# w5500_spi.net
KiCad netlist of a schematic drawn in EAGLE
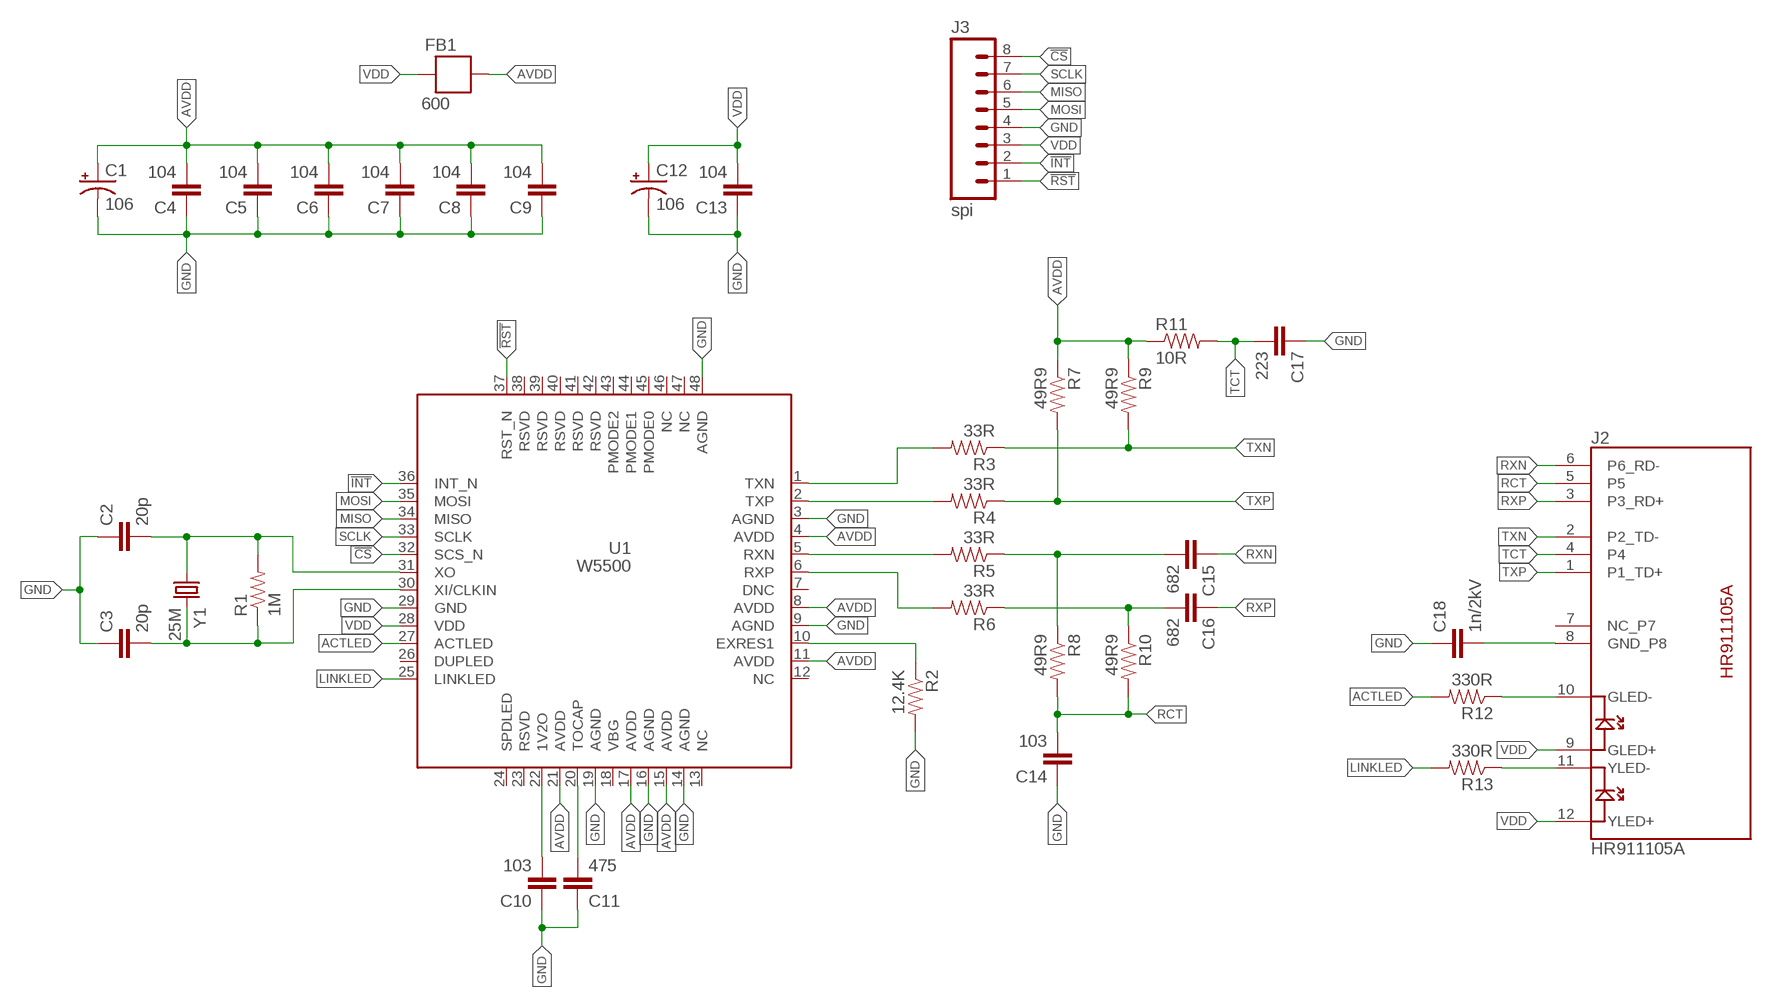
[diagram p0: schematic, sheet 1]

(export (version "E")
  (design (tool "Eeschema 10.0.6"))
  (components
    (comp (ref "C1")
      (value "106")
      (footprint "eagle-import:EIA3216")
      (libsource (lib "eagle-import") (part "CAP_POL1206"))
    )
    (comp (ref "C2")
      (value "20p")
      (footprint "eagle-import:0603-CAP")
      (libsource (lib "eagle-import") (part "z_jlc_smt_CAP0603-CAP"))
    )
    (comp (ref "C3")
      (value "20p")
      (footprint "eagle-import:0603-CAP")
      (libsource (lib "eagle-import") (part "z_jlc_smt_CAP0603-CAP"))
    )
    (comp (ref "C4")
      (value "104")
      (footprint "eagle-import:0603-CAP")
      (libsource (lib "eagle-import") (part "CAP0603-CAP"))
    )
    (comp (ref "C5")
      (value "104")
      (footprint "eagle-import:0603-CAP")
      (libsource (lib "eagle-import") (part "z_jlc_smt_CAP0603-CAP"))
    )
    (comp (ref "C6")
      (value "104")
      (footprint "eagle-import:0603-CAP")
      (libsource (lib "eagle-import") (part "z_jlc_smt_CAP0603-CAP"))
    )
    (comp (ref "C7")
      (value "104")
      (footprint "eagle-import:0603-CAP")
      (libsource (lib "eagle-import") (part "z_jlc_smt_CAP0603-CAP"))
    )
    (comp (ref "C8")
      (value "104")
      (footprint "eagle-import:0603-CAP")
      (libsource (lib "eagle-import") (part "z_jlc_smt_CAP0603-CAP"))
    )
    (comp (ref "C9")
      (value "104")
      (footprint "eagle-import:0603-CAP")
      (libsource (lib "eagle-import") (part "z_jlc_smt_CAP0603-CAP"))
    )
    (comp (ref "C10")
      (value "103")
      (footprint "eagle-import:0603-CAP")
      (libsource (lib "eagle-import") (part "z_jlc_smt_CAP0603-CAP"))
    )
    (comp (ref "C11")
      (value "475")
      (footprint "eagle-import:0603-CAP")
      (libsource (lib "eagle-import") (part "z_jlc_smt_CAP0603-CAP"))
    )
    (comp (ref "C12")
      (value "106")
      (footprint "eagle-import:EIA3216")
      (libsource (lib "eagle-import") (part "CAP_POL1206"))
    )
    (comp (ref "C13")
      (value "104")
      (footprint "eagle-import:0603-CAP")
      (libsource (lib "eagle-import") (part "z_jlc_smt_CAP0603-CAP"))
    )
    (comp (ref "C14")
      (value "103")
      (footprint "eagle-import:0603-CAP")
      (libsource (lib "eagle-import") (part "z_jlc_smt_CAP0603-CAP"))
    )
    (comp (ref "C15")
      (value "682")
      (footprint "eagle-import:0603-CAP")
      (libsource (lib "eagle-import") (part "z_jlc_smt_CAP0603-CAP"))
    )
    (comp (ref "C16")
      (value "682")
      (footprint "eagle-import:0603-CAP")
      (libsource (lib "eagle-import") (part "z_jlc_smt_CAP0603-CAP"))
    )
    (comp (ref "C17")
      (value "223")
      (footprint "eagle-import:0603-CAP")
      (libsource (lib "eagle-import") (part "z_jlc_smt_CAP0603-CAP"))
    )
    (comp (ref "C18")
      (value "1n/2kV")
      (footprint "eagle-import:1206")
      (libsource (lib "eagle-import") (part "z_jlc_smt_CAP1206"))
    )
    (comp (ref "FB1")
      (value "600")
      (footprint "eagle-import:0805")
      (libsource (lib "eagle-import") (part "FB0805"))
    )
    (comp (ref "J2")
      (value "HR911105A")
      (footprint "eagle-import:HR911105A")
      (libsource (lib "eagle-import") (part "HR911105A"))
    )
    (comp (ref "J3")
      (value "spi")
      (footprint "eagle-import:1X08_PIN1_NO_SILK")
      (libsource (lib "eagle-import") (part "M08NO_SILK"))
    )
    (comp (ref "R1")
      (value "1M")
      (footprint "eagle-import:0603-RES")
      (libsource (lib "eagle-import") (part "z_jlc_smt_RESISTOR0603"))
    )
    (comp (ref "R2")
      (value "12.4K")
      (footprint "eagle-import:0603-RES")
      (libsource (lib "eagle-import") (part "z_jlc_smt_RESISTOR0603"))
    )
    (comp (ref "R3")
      (value "33R")
      (footprint "eagle-import:0603-RES")
      (libsource (lib "eagle-import") (part "RESISTOR0603-RES"))
    )
    (comp (ref "R4")
      (value "33R")
      (footprint "eagle-import:0603-RES")
      (libsource (lib "eagle-import") (part "z_jlc_smt_RESISTOR0603"))
    )
    (comp (ref "R5")
      (value "33R")
      (footprint "eagle-import:0603-RES")
      (libsource (lib "eagle-import") (part "z_jlc_smt_RESISTOR0603"))
    )
    (comp (ref "R6")
      (value "33R")
      (footprint "eagle-import:0603-RES")
      (libsource (lib "eagle-import") (part "z_jlc_smt_RESISTOR0603"))
    )
    (comp (ref "R7")
      (value "49R9")
      (footprint "eagle-import:0603-RES")
      (libsource (lib "eagle-import") (part "z_jlc_smt_RESISTOR0603"))
    )
    (comp (ref "R8")
      (value "49R9")
      (footprint "eagle-import:0603-RES")
      (libsource (lib "eagle-import") (part "z_jlc_smt_RESISTOR0603"))
    )
    (comp (ref "R9")
      (value "49R9")
      (footprint "eagle-import:0603-RES")
      (libsource (lib "eagle-import") (part "z_jlc_smt_RESISTOR0603"))
    )
    (comp (ref "R10")
      (value "49R9")
      (footprint "eagle-import:0603-RES")
      (libsource (lib "eagle-import") (part "z_jlc_smt_RESISTOR0603"))
    )
    (comp (ref "R11")
      (value "10R")
      (footprint "eagle-import:0603-RES")
      (libsource (lib "eagle-import") (part "z_jlc_smt_RESISTOR0603"))
    )
    (comp (ref "R12")
      (value "330R")
      (footprint "eagle-import:0603-RES")
      (libsource (lib "eagle-import") (part "z_jlc_smt_RESISTOR0603"))
    )
    (comp (ref "R13")
      (value "330R")
      (footprint "eagle-import:0603-RES")
      (libsource (lib "eagle-import") (part "z_jlc_smt_RESISTOR0603"))
    )
    (comp (ref "U1")
      (value "W5500")
      (footprint "eagle-import:LQFP-48")
      (libsource (lib "eagle-import") (part "W5500"))
    )
    (comp (ref "Y1")
      (value "25M")
      (footprint "eagle-import:HC49US")
      (libsource (lib "eagle-import") (part "CRYSTALHC49US"))
    )
  )
  (nets
    (net (code "1") (name "/~{CS}") (class "Default")
      (node (ref "J3") (pin "8") (pinfunction "8_8") (pintype "passive"))
      (node (ref "U1") (pin "32") (pinfunction "SCS_N_32") (pintype "passive"))
    )
    (net (code "2") (name "/~{INT}") (class "Default")
      (node (ref "J3") (pin "2") (pinfunction "2_2") (pintype "passive"))
      (node (ref "U1") (pin "36") (pinfunction "INT_N_36") (pintype "passive"))
    )
    (net (code "3") (name "/~{RST}") (class "Default")
      (node (ref "J3") (pin "1") (pinfunction "1_1") (pintype "passive"))
      (node (ref "U1") (pin "37") (pinfunction "RST_N_37") (pintype "passive"))
    )
    (net (code "4") (name "ACTLED") (class "Default")
      (node (ref "R12") (pin "2") (pinfunction "2_2") (pintype "passive"))
      (node (ref "U1") (pin "27") (pinfunction "ACTLED_27") (pintype "passive"))
    )
    (net (code "5") (name "AVDD") (class "Default")
      (node (ref "C1") (pin "A") (pinfunction "+_A") (pintype "passive"))
      (node (ref "C4") (pin "2") (pinfunction "2_2") (pintype "passive"))
      (node (ref "C5") (pin "2") (pinfunction "2_2") (pintype "passive"))
      (node (ref "C6") (pin "2") (pinfunction "2_2") (pintype "passive"))
      (node (ref "C7") (pin "2") (pinfunction "2_2") (pintype "passive"))
      (node (ref "C8") (pin "2") (pinfunction "2_2") (pintype "passive"))
      (node (ref "C9") (pin "2") (pinfunction "2_2") (pintype "passive"))
      (node (ref "FB1") (pin "1") (pinfunction "P$1_1") (pintype "bidirectional"))
      (node (ref "R11") (pin "1") (pinfunction "1_1") (pintype "passive"))
      (node (ref "R7") (pin "1") (pinfunction "1_1") (pintype "passive"))
      (node (ref "R9") (pin "1") (pinfunction "1_1") (pintype "passive"))
      (node (ref "U1") (pin "11") (pinfunction "AVDD_11") (pintype "passive"))
      (node (ref "U1") (pin "15") (pinfunction "AVDD_15") (pintype "passive"))
      (node (ref "U1") (pin "17") (pinfunction "AVDD_17") (pintype "passive"))
      (node (ref "U1") (pin "21") (pinfunction "AVDD_21") (pintype "passive"))
      (node (ref "U1") (pin "4") (pinfunction "AVDD_4") (pintype "passive"))
      (node (ref "U1") (pin "8") (pinfunction "AVDD_8") (pintype "passive"))
    )
    (net (code "6") (name "GND") (class "Default")
      (node (ref "C1") (pin "C") (pinfunction "-_C") (pintype "passive"))
      (node (ref "C10") (pin "1") (pinfunction "1_1") (pintype "passive"))
      (node (ref "C11") (pin "1") (pinfunction "1_1") (pintype "passive"))
      (node (ref "C12") (pin "C") (pinfunction "-_C") (pintype "passive"))
      (node (ref "C13") (pin "1") (pinfunction "1_1") (pintype "passive"))
      (node (ref "C14") (pin "1") (pinfunction "1_1") (pintype "passive"))
      (node (ref "C17") (pin "1") (pinfunction "1_1") (pintype "passive"))
      (node (ref "C18") (pin "1") (pinfunction "1_1") (pintype "passive"))
      (node (ref "C2") (pin "1") (pinfunction "1_1") (pintype "passive"))
      (node (ref "C3") (pin "1") (pinfunction "1_1") (pintype "passive"))
      (node (ref "C4") (pin "1") (pinfunction "1_1") (pintype "passive"))
      (node (ref "C5") (pin "1") (pinfunction "1_1") (pintype "passive"))
      (node (ref "C6") (pin "1") (pinfunction "1_1") (pintype "passive"))
      (node (ref "C7") (pin "1") (pinfunction "1_1") (pintype "passive"))
      (node (ref "C8") (pin "1") (pinfunction "1_1") (pintype "passive"))
      (node (ref "C9") (pin "1") (pinfunction "1_1") (pintype "passive"))
      (node (ref "J3") (pin "4") (pinfunction "4_4") (pintype "passive"))
      (node (ref "R2") (pin "2") (pinfunction "2_2") (pintype "passive"))
      (node (ref "U1") (pin "14") (pinfunction "AGND_14") (pintype "passive"))
      (node (ref "U1") (pin "16") (pinfunction "AGND_16") (pintype "passive"))
      (node (ref "U1") (pin "19") (pinfunction "AGND_19") (pintype "passive"))
      (node (ref "U1") (pin "29") (pinfunction "GND_29") (pintype "passive"))
      (node (ref "U1") (pin "3") (pinfunction "AGND_3") (pintype "passive"))
      (node (ref "U1") (pin "48") (pinfunction "AGND_48") (pintype "passive"))
      (node (ref "U1") (pin "9") (pinfunction "AGND_9") (pintype "passive"))
    )
    (net (code "7") (name "LINKLED") (class "Default")
      (node (ref "R13") (pin "2") (pinfunction "2_2") (pintype "passive"))
      (node (ref "U1") (pin "25") (pinfunction "LINKLED_25") (pintype "passive"))
    )
    (net (code "8") (name "MISO") (class "Default")
      (node (ref "J3") (pin "6") (pinfunction "6_6") (pintype "passive"))
      (node (ref "U1") (pin "34") (pinfunction "MISO_34") (pintype "passive"))
    )
    (net (code "9") (name "MOSI") (class "Default")
      (node (ref "J3") (pin "5") (pinfunction "5_5") (pintype "passive"))
      (node (ref "U1") (pin "35") (pinfunction "MOSI_35") (pintype "passive"))
    )
    (net (code "10") (name "Net-(C15-Pad2)") (class "Default")
      (node (ref "C15") (pin "2") (pinfunction "2_2") (pintype "passive"))
      (node (ref "R5") (pin "1") (pinfunction "1_1") (pintype "passive"))
      (node (ref "R8") (pin "1") (pinfunction "1_1") (pintype "passive"))
    )
    (net (code "11") (name "Net-(C16-Pad2)") (class "Default")
      (node (ref "C16") (pin "2") (pinfunction "2_2") (pintype "passive"))
      (node (ref "R10") (pin "1") (pinfunction "1_1") (pintype "passive"))
      (node (ref "R6") (pin "1") (pinfunction "1_1") (pintype "passive"))
    )
    (net (code "12") (name "Net-(J2-GLED-)") (class "Default")
      (node (ref "J2") (pin "10") (pinfunction "GLED-_10") (pintype "bidirectional"))
      (node (ref "R12") (pin "1") (pinfunction "1_1") (pintype "passive"))
    )
    (net (code "13") (name "Net-(J2-GND_P8)") (class "Default")
      (node (ref "C18") (pin "2") (pinfunction "2_2") (pintype "passive"))
      (node (ref "J2") (pin "8") (pinfunction "GND_P8_8") (pintype "bidirectional"))
    )
    (net (code "14") (name "Net-(J2-YLED-)") (class "Default")
      (node (ref "J2") (pin "11") (pinfunction "YLED-_11") (pintype "bidirectional"))
      (node (ref "R13") (pin "1") (pinfunction "1_1") (pintype "passive"))
    )
    (net (code "15") (name "Net-(U1-1V2O)") (class "Default")
      (node (ref "C10") (pin "2") (pinfunction "2_2") (pintype "passive"))
      (node (ref "U1") (pin "22") (pinfunction "1V2O_22") (pintype "passive"))
    )
    (net (code "16") (name "Net-(U1-EXRES1)") (class "Default")
      (node (ref "R2") (pin "1") (pinfunction "1_1") (pintype "passive"))
      (node (ref "U1") (pin "10") (pinfunction "EXRES1_10") (pintype "passive"))
    )
    (net (code "17") (name "Net-(U1-RXN)") (class "Default")
      (node (ref "R5") (pin "2") (pinfunction "2_2") (pintype "passive"))
      (node (ref "U1") (pin "5") (pinfunction "RXN_5") (pintype "passive"))
    )
    (net (code "18") (name "Net-(U1-RXP)") (class "Default")
      (node (ref "R6") (pin "2") (pinfunction "2_2") (pintype "passive"))
      (node (ref "U1") (pin "6") (pinfunction "RXP_6") (pintype "passive"))
    )
    (net (code "19") (name "Net-(U1-TOCAP)") (class "Default")
      (node (ref "C11") (pin "2") (pinfunction "2_2") (pintype "passive"))
      (node (ref "U1") (pin "20") (pinfunction "TOCAP_20") (pintype "passive"))
    )
    (net (code "20") (name "Net-(U1-TXN)") (class "Default")
      (node (ref "R3") (pin "2") (pinfunction "2_2") (pintype "passive"))
      (node (ref "U1") (pin "1") (pinfunction "TXN_1") (pintype "passive"))
    )
    (net (code "21") (name "Net-(U1-TXP)") (class "Default")
      (node (ref "R4") (pin "2") (pinfunction "2_2") (pintype "passive"))
      (node (ref "U1") (pin "2") (pinfunction "TXP_2") (pintype "passive"))
    )
    (net (code "22") (name "Net-(U1-XI{slash}CLKIN)") (class "Default")
      (node (ref "C3") (pin "2") (pinfunction "2_2") (pintype "passive"))
      (node (ref "R1") (pin "1") (pinfunction "1_1") (pintype "passive"))
      (node (ref "U1") (pin "30") (pinfunction "XI/CLKIN_30") (pintype "passive"))
      (node (ref "Y1") (pin "2") (pinfunction "2_2") (pintype "passive"))
    )
    (net (code "23") (name "Net-(U1-XO)") (class "Default")
      (node (ref "C2") (pin "2") (pinfunction "2_2") (pintype "passive"))
      (node (ref "R1") (pin "2") (pinfunction "2_2") (pintype "passive"))
      (node (ref "U1") (pin "31") (pinfunction "XO_31") (pintype "passive"))
      (node (ref "Y1") (pin "1") (pinfunction "1_1") (pintype "passive"))
    )
    (net (code "24") (name "RCT") (class "Default")
      (node (ref "C14") (pin "2") (pinfunction "2_2") (pintype "passive"))
      (node (ref "J2") (pin "5") (pinfunction "P5_5") (pintype "bidirectional"))
      (node (ref "R10") (pin "2") (pinfunction "2_2") (pintype "passive"))
      (node (ref "R8") (pin "2") (pinfunction "2_2") (pintype "passive"))
    )
    (net (code "25") (name "RXN") (class "Default")
      (node (ref "C15") (pin "1") (pinfunction "1_1") (pintype "passive"))
      (node (ref "J2") (pin "6") (pinfunction "P6_RD-_6") (pintype "bidirectional"))
    )
    (net (code "26") (name "RXP") (class "Default")
      (node (ref "C16") (pin "1") (pinfunction "1_1") (pintype "passive"))
      (node (ref "J2") (pin "3") (pinfunction "P3_RD+_3") (pintype "bidirectional"))
    )
    (net (code "27") (name "SCLK") (class "Default")
      (node (ref "J3") (pin "7") (pinfunction "7_7") (pintype "passive"))
      (node (ref "U1") (pin "33") (pinfunction "SCLK_33") (pintype "passive"))
    )
    (net (code "28") (name "TCT") (class "Default")
      (node (ref "C17") (pin "2") (pinfunction "2_2") (pintype "passive"))
      (node (ref "J2") (pin "4") (pinfunction "P4_4") (pintype "bidirectional"))
      (node (ref "R11") (pin "2") (pinfunction "2_2") (pintype "passive"))
    )
    (net (code "29") (name "TXN") (class "Default")
      (node (ref "J2") (pin "2") (pinfunction "P2_TD-_2") (pintype "bidirectional"))
      (node (ref "R3") (pin "1") (pinfunction "1_1") (pintype "passive"))
      (node (ref "R9") (pin "2") (pinfunction "2_2") (pintype "passive"))
    )
    (net (code "30") (name "TXP") (class "Default")
      (node (ref "J2") (pin "1") (pinfunction "P1_TD+_1") (pintype "bidirectional"))
      (node (ref "R4") (pin "1") (pinfunction "1_1") (pintype "passive"))
      (node (ref "R7") (pin "2") (pinfunction "2_2") (pintype "passive"))
    )
    (net (code "31") (name "VDD") (class "Default")
      (node (ref "C12") (pin "A") (pinfunction "+_A") (pintype "passive"))
      (node (ref "C13") (pin "2") (pinfunction "2_2") (pintype "passive"))
      (node (ref "FB1") (pin "2") (pinfunction "P$2_2") (pintype "bidirectional"))
      (node (ref "J2") (pin "12") (pinfunction "YLED+_12") (pintype "bidirectional"))
      (node (ref "J2") (pin "9") (pinfunction "GLED+_9") (pintype "bidirectional"))
      (node (ref "J3") (pin "3") (pinfunction "3_3") (pintype "passive"))
      (node (ref "U1") (pin "28") (pinfunction "VDD_28") (pintype "passive"))
    )
    (net (code "32") (name "unconnected-(J2-NC_P7-Pad7)") (class "Default")
      (node (ref "J2") (pin "7") (pinfunction "NC_P7_7") (pintype "bidirectional"))
    )
    (net (code "33") (name "unconnected-(U1-DNC-Pad7)") (class "Default")
      (node (ref "U1") (pin "7") (pinfunction "DNC_7") (pintype "passive"))
    )
    (net (code "34") (name "unconnected-(U1-DUPLED-Pad26)") (class "Default")
      (node (ref "U1") (pin "26") (pinfunction "DUPLED_26") (pintype "passive"))
    )
    (net (code "35") (name "unconnected-(U1-NC-Pad12)") (class "Default")
      (node (ref "U1") (pin "12") (pinfunction "NC_12") (pintype "passive"))
    )
    (net (code "36") (name "unconnected-(U1-NC-Pad13)") (class "Default")
      (node (ref "U1") (pin "13") (pinfunction "NC_13") (pintype "passive"))
    )
    (net (code "37") (name "unconnected-(U1-NC-Pad46)") (class "Default")
      (node (ref "U1") (pin "46") (pinfunction "NC_46") (pintype "passive"))
    )
    (net (code "38") (name "unconnected-(U1-NC-Pad47)") (class "Default")
      (node (ref "U1") (pin "47") (pinfunction "NC_47") (pintype "passive"))
    )
    (net (code "39") (name "unconnected-(U1-PMODE0-Pad45)") (class "Default")
      (node (ref "U1") (pin "45") (pinfunction "PMODE0_45") (pintype "passive"))
    )
    (net (code "40") (name "unconnected-(U1-PMODE1-Pad44)") (class "Default")
      (node (ref "U1") (pin "44") (pinfunction "PMODE1_44") (pintype "passive"))
    )
    (net (code "41") (name "unconnected-(U1-PMODE2-Pad43)") (class "Default")
      (node (ref "U1") (pin "43") (pinfunction "PMODE2_43") (pintype "passive"))
    )
    (net (code "42") (name "unconnected-(U1-RSVD-Pad23)") (class "Default")
      (node (ref "U1") (pin "23") (pinfunction "RSVD_23") (pintype "passive"))
    )
    (net (code "43") (name "unconnected-(U1-RSVD-Pad38)") (class "Default")
      (node (ref "U1") (pin "38") (pinfunction "RSVD_38") (pintype "passive"))
    )
    (net (code "44") (name "unconnected-(U1-RSVD-Pad39)") (class "Default")
      (node (ref "U1") (pin "39") (pinfunction "RSVD_39") (pintype "passive"))
    )
    (net (code "45") (name "unconnected-(U1-RSVD-Pad40)") (class "Default")
      (node (ref "U1") (pin "40") (pinfunction "RSVD_40") (pintype "passive"))
    )
    (net (code "46") (name "unconnected-(U1-RSVD-Pad41)") (class "Default")
      (node (ref "U1") (pin "41") (pinfunction "RSVD_41") (pintype "passive"))
    )
    (net (code "47") (name "unconnected-(U1-RSVD-Pad42)") (class "Default")
      (node (ref "U1") (pin "42") (pinfunction "RSVD_42") (pintype "passive"))
    )
    (net (code "48") (name "unconnected-(U1-SPDLED-Pad24)") (class "Default")
      (node (ref "U1") (pin "24") (pinfunction "SPDLED_24") (pintype "passive"))
    )
    (net (code "49") (name "unconnected-(U1-VBG-Pad18)") (class "Default")
      (node (ref "U1") (pin "18") (pinfunction "VBG_18") (pintype "passive"))
    )
  )
)
